# main.net
KiCad netlist of a schematic drawn in Altium Designer
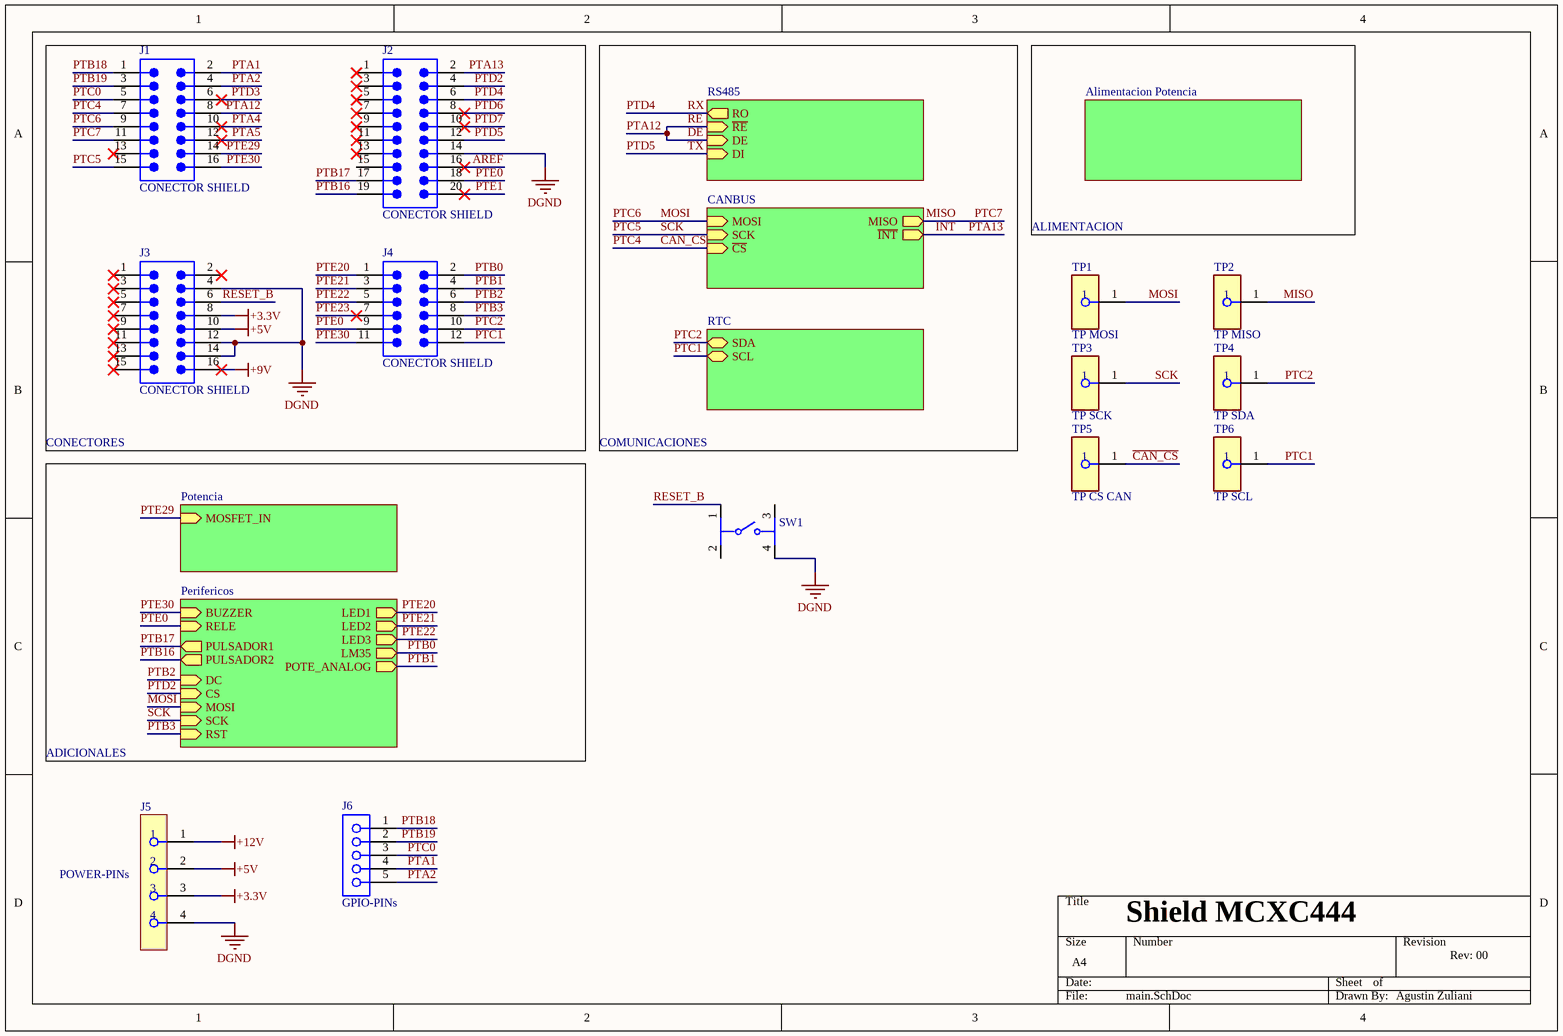
[diagram p0: main.SchDoc]

(export (version "E")
  (design (tool "Eeschema 10.0.6"))
  (components
    (comp (ref "J1")
      (value "CONECTOR SHIELD")
      (footprint "61301621121")
      (description "HEADER PINS 16 POS 2.54mm / Conexion shield")
      (libsource (lib "Altium Content Vault") (part "Header_Male_2R_16P"))
    )
    (comp (ref "J2")
      (value "CONECTOR SHIELD")
      (footprint "61302021121")
      (description "HEADER PINS 20 POS 2.54mm / Conexion shield")
      (libsource (lib "Altium Content Vault") (part "Header_Male_2R_20P"))
    )
    (comp (ref "J3")
      (value "CONECTOR SHIELD")
      (footprint "61301621121")
      (description "HEADER PINS 16 POS 2.54mm / Conexion shield")
      (libsource (lib "Altium Content Vault") (part "Header_Male_2R_16P"))
    )
    (comp (ref "J4")
      (value "CONECTOR SHIELD")
      (footprint "61301221121")
      (description "HEADER PINS 12 POS 2.54mm / Conexion shield")
      (libsource (lib "Altium Content Vault") (part "Header_Male_2R_12P"))
    )
    (comp (ref "J5")
      (value "POWER-PINs")
      (footprint "FP-ESW-104-23-G-S-MFG")
      (description "HEADER PINS 4 POS 2.54mm / Power Pins")
      (libsource (lib "Altium Content Vault") (part "ESW-104-23-G-S"))
    )
    (comp (ref "J6")
      (value "GPIO-PINs")
      (footprint "SMTC-SMH-105-02-X-S")
      (description "HEADER PINS 5 POS / Gpios Pins")
      (fields (field (name "PARTNUMBER") "SMH-105-02-G-S") (field (name "MANUFACTURER") "Samtec"))
      (libsource (lib "Altium Content Vault") (part "SMTC-SMH-105-02-X-S"))
    )
    (comp (ref "SW1")
      (value "PULSADOR RESET")
      (footprint "FP-1-1825910-4-MFG")
      (description "SWITCH TACTILE 6mm / RESET")
      (fields
        (field (name "OCTOPART") "https://octopart.com/1-1825910-4-te+connectivity-42270468")
        (field (name "MANUFACTURER") "TE Connectivity")
      )
      (libsource (lib "Altium Content Vault") (part "b8895f3f4cefb76e1819d2863dba89b"))
    )
    (comp (ref "TP1")
      (value "TP MOSI")
      (footprint "FP-5004-MFG")
      (description "PC TEST POINT MINIATURE YELLOW")
      (fields (field (name "MANUFACTURER") "Keystone") (field (name "MANUFACTURER PART NUMBER") "5004"))
      (libsource (lib "Altium Content Vault") (part "98815daf2f2c152b0c43f5ab9800df6"))
    )
    (comp (ref "TP2")
      (value "TP MISO")
      (footprint "FP-5004-MFG")
      (description "PC TEST POINT MINIATURE YELLOW")
      (fields (field (name "MANUFACTURER") "Keystone") (field (name "MANUFACTURER PART NUMBER") "5004"))
      (libsource (lib "Altium Content Vault") (part "98815daf2f2c152b0c43f5ab9800df6"))
    )
    (comp (ref "TP3")
      (value "TP SCK")
      (footprint "FP-5004-MFG")
      (description "PC TEST POINT MINIATURE YELLOW")
      (fields (field (name "MANUFACTURER") "Keystone") (field (name "MANUFACTURER PART NUMBER") "5004"))
      (libsource (lib "Altium Content Vault") (part "98815daf2f2c152b0c43f5ab9800df6"))
    )
    (comp (ref "TP4")
      (value "TP SDA")
      (footprint "FP-5004-MFG")
      (description "PC TEST POINT MINIATURE YELLOW")
      (fields (field (name "MANUFACTURER") "Keystone") (field (name "MANUFACTURER PART NUMBER") "5004"))
      (libsource (lib "Altium Content Vault") (part "98815daf2f2c152b0c43f5ab9800df6"))
    )
    (comp (ref "TP5")
      (value "TP CS CAN")
      (footprint "FP-5004-MFG")
      (description "PC TEST POINT MINIATURE YELLOW")
      (fields (field (name "MANUFACTURER") "Keystone") (field (name "MANUFACTURER PART NUMBER") "5004"))
      (libsource (lib "Altium Content Vault") (part "98815daf2f2c152b0c43f5ab9800df6"))
    )
    (comp (ref "TP6")
      (value "TP SCL")
      (footprint "FP-5004-MFG")
      (description "PC TEST POINT MINIATURE YELLOW")
      (fields (field (name "MANUFACTURER") "Keystone") (field (name "MANUFACTURER PART NUMBER") "5004"))
      (libsource (lib "Altium Content Vault") (part "98815daf2f2c152b0c43f5ab9800df6"))
    )
  )
  (nets
    (net (code "1") (name "+3.3V") (class "Default")
      (node (ref "J3") (pin "8") (pinfunction "8_8") (pintype "passive"))
      (node (ref "J5") (pin "3") (pinfunction "3_3") (pintype "passive"))
    )
    (net (code "2") (name "+5V") (class "Default")
      (node (ref "J3") (pin "10") (pinfunction "10_10") (pintype "passive"))
      (node (ref "J5") (pin "2") (pinfunction "2_2") (pintype "passive"))
    )
    (net (code "3") (name "+9V") (class "Default")
      (node (ref "J3") (pin "16") (pinfunction "16_16") (pintype "passive"))
    )
    (net (code "4") (name "+12V") (class "Default")
      (node (ref "J5") (pin "1") (pinfunction "1_1") (pintype "passive"))
    )
    (net (code "5") (name "/AREF") (class "Default")
      (node (ref "J2") (pin "16") (pinfunction "16_16") (pintype "passive+no_connect"))
    )
    (net (code "6") (name "/CAN_CS") (class "Default")
      (node (ref "J1") (pin "7") (pinfunction "7_7") (pintype "passive"))
      (node (ref "TP5") (pin "1") (pinfunction "1_1") (pintype "passive"))
    )
    (net (code "7") (name "/DE") (class "Default")
      (node (ref "J1") (pin "8") (pinfunction "8_8") (pintype "passive"))
    )
    (net (code "8") (name "/INT") (class "Default")
      (node (ref "J2") (pin "2") (pinfunction "2_2") (pintype "passive"))
    )
    (net (code "9") (name "/MISO") (class "Default")
      (node (ref "J1") (pin "11") (pinfunction "11_11") (pintype "passive"))
      (node (ref "TP2") (pin "1") (pinfunction "1_1") (pintype "passive"))
    )
    (net (code "10") (name "/MOSI") (class "Default")
      (node (ref "J1") (pin "9") (pinfunction "9_9") (pintype "passive"))
      (node (ref "TP1") (pin "1") (pinfunction "1_1") (pintype "passive"))
    )
    (net (code "11") (name "/PTA1") (class "Default")
      (node (ref "J1") (pin "2") (pinfunction "2_2") (pintype "passive"))
      (node (ref "J6") (pin "4") (pinfunction "4_4") (pintype "passive"))
    )
    (net (code "12") (name "/PTA2") (class "Default")
      (node (ref "J1") (pin "4") (pinfunction "4_4") (pintype "passive"))
      (node (ref "J6") (pin "5") (pinfunction "5_5") (pintype "passive"))
    )
    (net (code "13") (name "/PTA4") (class "Default")
      (node (ref "J1") (pin "10") (pinfunction "10_10") (pintype "passive+no_connect"))
    )
    (net (code "14") (name "/PTA5") (class "Default")
      (node (ref "J1") (pin "12") (pinfunction "12_12") (pintype "passive+no_connect"))
    )
    (net (code "15") (name "/PTB0") (class "Default")
      (node (ref "J4") (pin "2") (pinfunction "2_2") (pintype "passive"))
    )
    (net (code "16") (name "/PTB1") (class "Default")
      (node (ref "J4") (pin "4") (pinfunction "4_4") (pintype "passive"))
    )
    (net (code "17") (name "/PTB2") (class "Default")
      (node (ref "J4") (pin "6") (pinfunction "6_6") (pintype "passive"))
    )
    (net (code "18") (name "/PTB3") (class "Default")
      (node (ref "J4") (pin "8") (pinfunction "8_8") (pintype "passive"))
    )
    (net (code "19") (name "/PTB16") (class "Default")
      (node (ref "J2") (pin "19") (pinfunction "19_19") (pintype "passive"))
    )
    (net (code "20") (name "/PTB17") (class "Default")
      (node (ref "J2") (pin "17") (pinfunction "17_17") (pintype "passive"))
    )
    (net (code "21") (name "/PTB18") (class "Default")
      (node (ref "J1") (pin "1") (pinfunction "1_1") (pintype "passive"))
      (node (ref "J6") (pin "1") (pinfunction "1_1") (pintype "passive"))
    )
    (net (code "22") (name "/PTB19") (class "Default")
      (node (ref "J1") (pin "3") (pinfunction "3_3") (pintype "passive"))
      (node (ref "J6") (pin "2") (pinfunction "2_2") (pintype "passive"))
    )
    (net (code "23") (name "/PTC0") (class "Default")
      (node (ref "J1") (pin "5") (pinfunction "5_5") (pintype "passive"))
      (node (ref "J6") (pin "3") (pinfunction "3_3") (pintype "passive"))
    )
    (net (code "24") (name "/PTC1") (class "Default")
      (node (ref "J4") (pin "12") (pinfunction "12_12") (pintype "passive"))
      (node (ref "TP6") (pin "1") (pinfunction "1_1") (pintype "passive"))
    )
    (net (code "25") (name "/PTC2") (class "Default")
      (node (ref "J4") (pin "10") (pinfunction "10_10") (pintype "passive"))
      (node (ref "TP4") (pin "1") (pinfunction "1_1") (pintype "passive"))
    )
    (net (code "26") (name "/PTC5") (class "Default")
      (node (ref "J1") (pin "15") (pinfunction "15_15") (pintype "passive"))
      (node (ref "TP3") (pin "1") (pinfunction "1_1") (pintype "passive"))
    )
    (net (code "27") (name "/PTD2") (class "Default")
      (node (ref "J2") (pin "4") (pinfunction "4_4") (pintype "passive"))
    )
    (net (code "28") (name "/PTD3") (class "Default")
      (node (ref "J1") (pin "6") (pinfunction "6_6") (pintype "passive+no_connect"))
    )
    (net (code "29") (name "/PTD4") (class "Default")
      (node (ref "J2") (pin "6") (pinfunction "6_6") (pintype "passive"))
    )
    (net (code "30") (name "/PTD5") (class "Default")
      (node (ref "J2") (pin "12") (pinfunction "12_12") (pintype "passive"))
    )
    (net (code "31") (name "/PTD6") (class "Default")
      (node (ref "J2") (pin "8") (pinfunction "8_8") (pintype "passive+no_connect"))
    )
    (net (code "32") (name "/PTD7") (class "Default")
      (node (ref "J2") (pin "10") (pinfunction "10_10") (pintype "passive+no_connect"))
    )
    (net (code "33") (name "/PTE0") (class "Default")
      (node (ref "J2") (pin "18") (pinfunction "18_18") (pintype "passive"))
      (node (ref "J4") (pin "9") (pinfunction "9_9") (pintype "passive"))
    )
    (net (code "34") (name "/PTE1") (class "Default")
      (node (ref "J2") (pin "20") (pinfunction "20_20") (pintype "passive+no_connect"))
    )
    (net (code "35") (name "/PTE20") (class "Default")
      (node (ref "J4") (pin "1") (pinfunction "1_1") (pintype "passive"))
    )
    (net (code "36") (name "/PTE21") (class "Default")
      (node (ref "J4") (pin "3") (pinfunction "3_3") (pintype "passive"))
    )
    (net (code "37") (name "/PTE22") (class "Default")
      (node (ref "J4") (pin "5") (pinfunction "5_5") (pintype "passive"))
    )
    (net (code "38") (name "/PTE23") (class "Default")
      (node (ref "J4") (pin "7") (pinfunction "7_7") (pintype "passive+no_connect"))
    )
    (net (code "39") (name "/PTE29") (class "Default")
      (node (ref "J1") (pin "14") (pinfunction "14_14") (pintype "passive"))
    )
    (net (code "40") (name "/PTE30") (class "Default")
      (node (ref "J1") (pin "16") (pinfunction "16_16") (pintype "passive"))
      (node (ref "J4") (pin "11") (pinfunction "11_11") (pintype "passive"))
    )
    (net (code "41") (name "/RESET_B") (class "Default")
      (node (ref "J3") (pin "6") (pinfunction "6_6") (pintype "passive"))
      (node (ref "SW1") (pin "1") (pinfunction "1_1") (pintype "passive"))
    )
    (net (code "42") (name "DGND") (class "Default")
      (node (ref "J2") (pin "14") (pinfunction "14_14") (pintype "passive"))
      (node (ref "J3") (pin "12") (pinfunction "12_12") (pintype "passive"))
      (node (ref "J3") (pin "14") (pinfunction "14_14") (pintype "passive"))
      (node (ref "J3") (pin "4") (pinfunction "4_4") (pintype "passive"))
      (node (ref "J5") (pin "4") (pinfunction "4_4") (pintype "passive"))
      (node (ref "SW1") (pin "4") (pinfunction "4_4") (pintype "passive"))
    )
    (net (code "43") (name "unconnected-(J1-Pad13)") (class "Default")
      (node (ref "J1") (pin "13") (pinfunction "13_13") (pintype "passive+no_connect"))
    )
    (net (code "44") (name "unconnected-(J2-Pad1)") (class "Default")
      (node (ref "J2") (pin "1") (pinfunction "1_1") (pintype "passive+no_connect"))
    )
    (net (code "45") (name "unconnected-(J2-Pad3)") (class "Default")
      (node (ref "J2") (pin "3") (pinfunction "3_3") (pintype "passive+no_connect"))
    )
    (net (code "46") (name "unconnected-(J2-Pad5)") (class "Default")
      (node (ref "J2") (pin "5") (pinfunction "5_5") (pintype "passive+no_connect"))
    )
    (net (code "47") (name "unconnected-(J2-Pad7)") (class "Default")
      (node (ref "J2") (pin "7") (pinfunction "7_7") (pintype "passive+no_connect"))
    )
    (net (code "48") (name "unconnected-(J2-Pad9)") (class "Default")
      (node (ref "J2") (pin "9") (pinfunction "9_9") (pintype "passive+no_connect"))
    )
    (net (code "49") (name "unconnected-(J2-Pad11)") (class "Default")
      (node (ref "J2") (pin "11") (pinfunction "11_11") (pintype "passive+no_connect"))
    )
    (net (code "50") (name "unconnected-(J2-Pad13)") (class "Default")
      (node (ref "J2") (pin "13") (pinfunction "13_13") (pintype "passive+no_connect"))
    )
    (net (code "51") (name "unconnected-(J2-Pad15)") (class "Default")
      (node (ref "J2") (pin "15") (pinfunction "15_15") (pintype "passive"))
    )
    (net (code "52") (name "unconnected-(J3-Pad1)") (class "Default")
      (node (ref "J3") (pin "1") (pinfunction "1_1") (pintype "passive+no_connect"))
    )
    (net (code "53") (name "unconnected-(J3-Pad2)") (class "Default")
      (node (ref "J3") (pin "2") (pinfunction "2_2") (pintype "passive+no_connect"))
    )
    (net (code "54") (name "unconnected-(J3-Pad3)") (class "Default")
      (node (ref "J3") (pin "3") (pinfunction "3_3") (pintype "passive+no_connect"))
    )
    (net (code "55") (name "unconnected-(J3-Pad5)") (class "Default")
      (node (ref "J3") (pin "5") (pinfunction "5_5") (pintype "passive+no_connect"))
    )
    (net (code "56") (name "unconnected-(J3-Pad7)") (class "Default")
      (node (ref "J3") (pin "7") (pinfunction "7_7") (pintype "passive+no_connect"))
    )
    (net (code "57") (name "unconnected-(J3-Pad9)") (class "Default")
      (node (ref "J3") (pin "9") (pinfunction "9_9") (pintype "passive+no_connect"))
    )
    (net (code "58") (name "unconnected-(J3-Pad11)") (class "Default")
      (node (ref "J3") (pin "11") (pinfunction "11_11") (pintype "passive+no_connect"))
    )
    (net (code "59") (name "unconnected-(J3-Pad13)") (class "Default")
      (node (ref "J3") (pin "13") (pinfunction "13_13") (pintype "passive+no_connect"))
    )
    (net (code "60") (name "unconnected-(J3-Pad15)") (class "Default")
      (node (ref "J3") (pin "15") (pinfunction "15_15") (pintype "passive+no_connect"))
    )
    (net (code "61") (name "unconnected-(SW1-Pad2)") (class "Default")
      (node (ref "SW1") (pin "2") (pinfunction "2_2") (pintype "passive"))
    )
    (net (code "62") (name "unconnected-(SW1-Pad3)") (class "Default")
      (node (ref "SW1") (pin "3") (pinfunction "3_3") (pintype "passive"))
    )
  )
)
